# Sheet.net
KiCad netlist of a schematic drawn in Altium Designer
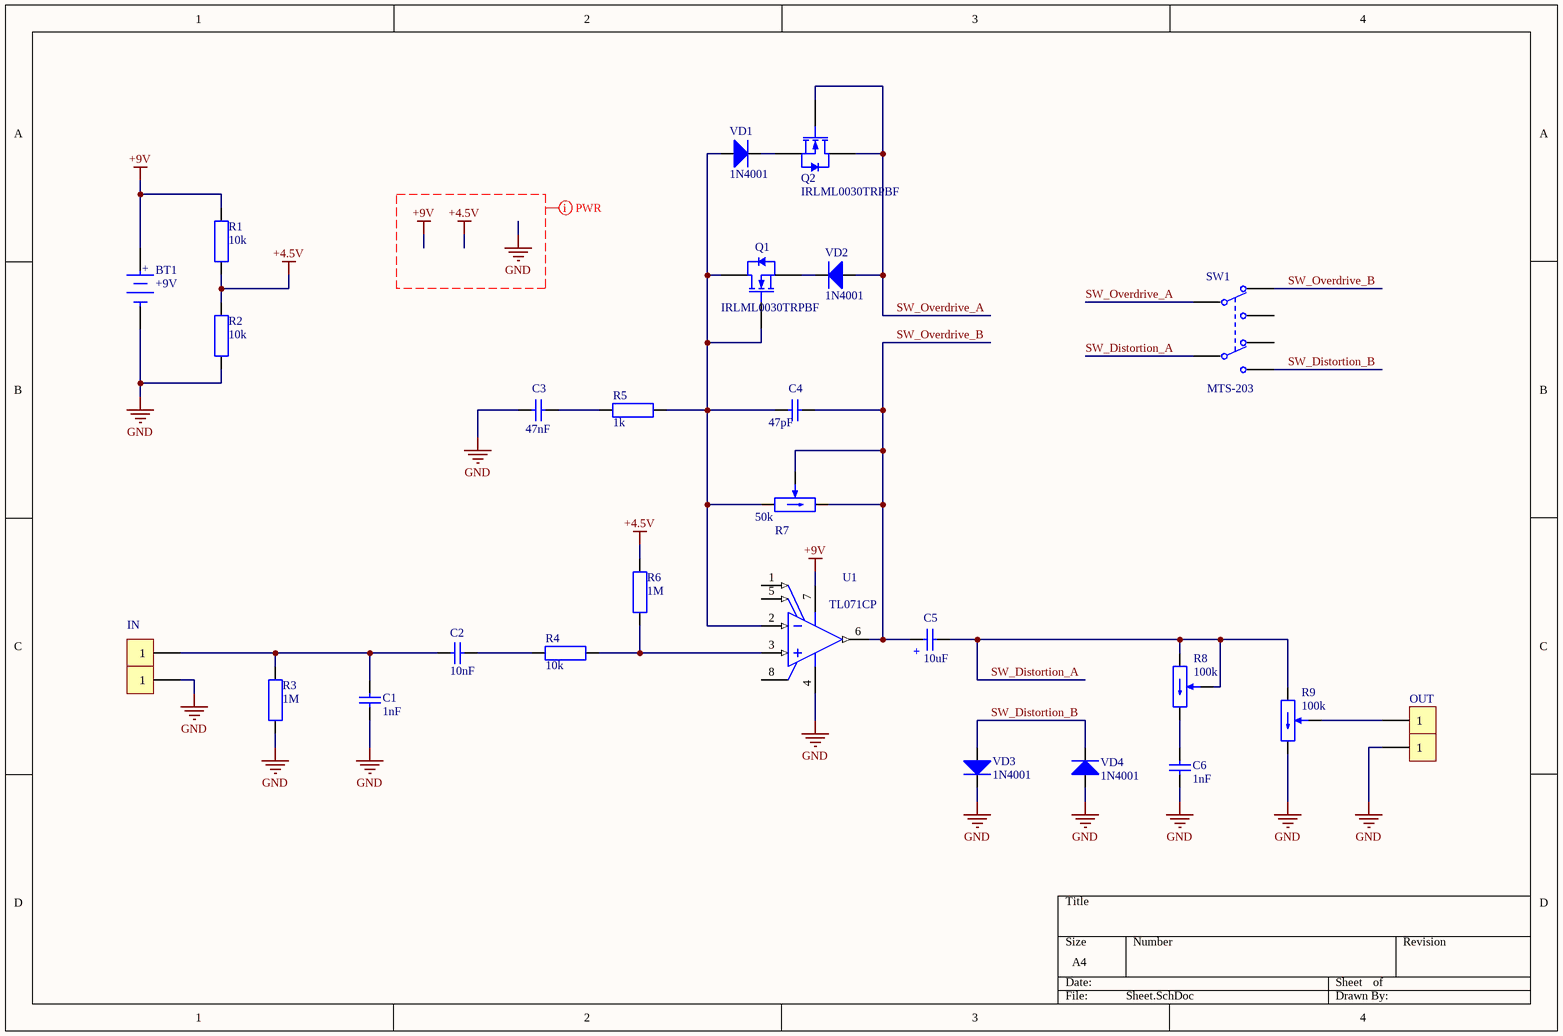
[diagram p0: Sheet.SchDoc]

(export (version "E")
  (design (tool "Eeschema 10.0.6"))
  (components
    (comp (ref "BT1")
      (value "+9V")
      (footprint "Power socket Mirrored")
      (libsource (lib "AD_lib_ISO") (part "Battery"))
    )
    (comp (ref "C1") (value "1nF") (footprint "CAP-CER-DISK") (libsource (lib "AD_lib_ISO") (part "Cap")))
    (comp (ref "C2") (value "10nF") (footprint "CAP-CER-DISK") (libsource (lib "AD_lib_ISO") (part "Cap")))
    (comp (ref "C3") (value "47nF") (footprint "CAP-CER-DISK") (libsource (lib "AD_lib_ISO") (part "Cap")))
    (comp (ref "C4") (value "47pF") (footprint "CAP-CER-DISK") (libsource (lib "AD_lib_ISO") (part "Cap")))
    (comp (ref "C5")
      (value "10uF")
      (footprint "CAP-ELEC-5x11mm")
      (libsource (lib "AD_lib_ISO") (part "Cap_Polar"))
    )
    (comp (ref "C6") (value "1nF") (footprint "CAP-CER-DISK") (libsource (lib "AD_lib_ISO") (part "Cap")))
    (comp (ref "IN+") (value "IN") (footprint "PLS-1") (libsource (lib "") (part "PLS-1_1")))
    (comp (ref "IN-") (value "PLS-1") (footprint "PLS-1") (libsource (lib "") (part "PLS-1_1")))
    (comp (ref "OUT+") (value "OUT") (footprint "PLS-1") (libsource (lib "AD_lib_ISO") (part "PLS-1")))
    (comp (ref "OUT-") (value "OUT") (footprint "PLS-1") (libsource (lib "AD_lib_ISO") (part "PLS-1")))
    (comp (ref "Q1")
      (value "IRLML0030TRPBF")
      (footprint "TO220 - HORIZONTAL")
      (fields (field (name "MANUFACTURER") "Infineon Technologies") (field (name "AUTHOR") "Tarasov Maxim"))
      (libsource (lib "AD_lib_ISO") (part "MOSFET N-CH"))
    )
    (comp (ref "Q2")
      (value "IRLML0030TRPBF")
      (footprint "TO220 - HORIZONTAL")
      (fields (field (name "MANUFACTURER") "Infineon Technologies") (field (name "AUTHOR") "Tarasov Maxim"))
      (libsource (lib "AD_lib_ISO") (part "MOSFET N-CH"))
    )
    (comp (ref "R1") (value "10k") (footprint "Res-Axis") (libsource (lib "AD_lib_ISO") (part "Res")))
    (comp (ref "R2") (value "10k") (footprint "Res-Axis") (libsource (lib "AD_lib_ISO") (part "Res")))
    (comp (ref "R3") (value "1M") (footprint "Res-Axis") (libsource (lib "AD_lib_ISO") (part "Res")))
    (comp (ref "R4") (value "10k") (footprint "Res-Axis") (libsource (lib "") (part "Res_1")))
    (comp (ref "R5") (value "1k") (footprint "Res-Axis") (libsource (lib "") (part "Res_1")))
    (comp (ref "R6") (value "1M") (footprint "Res-Axis") (libsource (lib "AD_lib_ISO") (part "Res")))
    (comp (ref "R7") (value "50k") (footprint "RES-POT-2") (libsource (lib "") (part "Res_Pot_1")))
    (comp (ref "R8") (value "100k") (footprint "RES-POT-2") (libsource (lib "AD_lib_ISO") (part "Res_Pot")))
    (comp (ref "R9") (value "100k") (footprint "RES-POT-2") (libsource (lib "AD_lib_ISO") (part "Res_Pot")))
    (comp (ref "SW1")
      (value "MTS-203")
      (footprint "MTS-203")
      (description "DPDT")
      (libsource (lib "AD_lib_ISO") (part "MTS-203"))
    )
    (comp (ref "U1")
      (value "TL071CP")
      (footprint "DIP-8")
      (fields (field (name "MANUFACTURER") "Texas Instruments"))
      (libsource (lib "AD_lib_ISO") (part "TL071CP"))
    )
    (comp (ref "VD1") (value "1N4001") (footprint "DIODE-AXIS") (libsource (lib "AD_lib_ISO") (part "Diode")))
    (comp (ref "VD2") (value "1N4001") (footprint "DIODE-AXIS") (libsource (lib "AD_lib_ISO") (part "Diode")))
    (comp (ref "VD3") (value "1N4001") (footprint "DIODE-AXIS") (libsource (lib "AD_lib_ISO") (part "Diode")))
    (comp (ref "VD4") (value "1N4001") (footprint "DIODE-AXIS") (libsource (lib "AD_lib_ISO") (part "Diode")))
  )
  (nets
    (net (code "1") (name "+4.5V") (class "Default")
      (node (ref "R1") (pin "1") (pinfunction "1_1") (pintype "passive"))
      (node (ref "R2") (pin "2") (pinfunction "2_2") (pintype "passive"))
      (node (ref "R6") (pin "2") (pinfunction "2_2") (pintype "passive"))
    )
    (net (code "2") (name "+9V") (class "Default")
      (node (ref "BT1") (pin "V") (pinfunction "A_V") (pintype "passive"))
      (node (ref "R1") (pin "2") (pinfunction "2_2") (pintype "passive"))
      (node (ref "U1") (pin "7") (pinfunction "VCC+_7") (pintype "power_in"))
    )
    (net (code "3") (name "/SW_Distortion_A") (class "Default")
      (node (ref "C5") (pin "C") (pinfunction "C_C") (pintype "passive"))
      (node (ref "R8") (pin "1") (pinfunction "CCW_1") (pintype "passive"))
      (node (ref "R8") (pin "3") (pinfunction "W_3") (pintype "passive"))
      (node (ref "R9") (pin "1") (pinfunction "CCW_1") (pintype "passive"))
      (node (ref "SW1") (pin "5") (pinfunction "5_5") (pintype "passive"))
    )
    (net (code "4") (name "/SW_Distortion_B") (class "Default")
      (node (ref "SW1") (pin "6") (pinfunction "6_6") (pintype "passive"))
      (node (ref "VD3") (pin "A") (pinfunction "A_A") (pintype "passive"))
      (node (ref "VD4") (pin "C") (pinfunction "C_C") (pintype "passive"))
    )
    (net (code "5") (name "/SW_Overdrive_A") (class "Default")
      (node (ref "Q2") (pin "1") (pinfunction "G_1") (pintype "passive"))
      (node (ref "Q2") (pin "2") (pinfunction "D_2") (pintype "passive"))
      (node (ref "SW1") (pin "2") (pinfunction "2_2") (pintype "passive"))
      (node (ref "VD2") (pin "A") (pinfunction "A_A") (pintype "passive"))
    )
    (net (code "6") (name "/SW_Overdrive_B") (class "Default")
      (node (ref "C4") (pin "2") (pinfunction "2_2") (pintype "passive"))
      (node (ref "C5") (pin "A") (pinfunction "A_A") (pintype "passive"))
      (node (ref "R7") (pin "2") (pinfunction "CW_2") (pintype "passive"))
      (node (ref "R7") (pin "3") (pinfunction "W_3") (pintype "passive"))
      (node (ref "SW1") (pin "3") (pinfunction "3_3") (pintype "passive"))
      (node (ref "U1") (pin "6") (pinfunction "OUT_6") (pintype "output"))
    )
    (net (code "7") (name "GND") (class "Default")
      (node (ref "BT1") (pin "G") (pinfunction "C_G") (pintype "passive"))
      (node (ref "C1") (pin "2") (pinfunction "2_2") (pintype "passive"))
      (node (ref "C3") (pin "1") (pinfunction "1_1") (pintype "passive"))
      (node (ref "C6") (pin "2") (pinfunction "2_2") (pintype "passive"))
      (node (ref "IN-") (pin "1") (pinfunction "1_1") (pintype "passive"))
      (node (ref "OUT-") (pin "1") (pinfunction "1_1") (pintype "passive"))
      (node (ref "R2") (pin "1") (pinfunction "1_1") (pintype "passive"))
      (node (ref "R3") (pin "1") (pinfunction "1_1") (pintype "passive"))
      (node (ref "R9") (pin "2") (pinfunction "CW_2") (pintype "passive"))
      (node (ref "U1") (pin "4") (pinfunction "VCC-_4") (pintype "power_in"))
      (node (ref "VD3") (pin "C") (pinfunction "C_C") (pintype "passive"))
      (node (ref "VD4") (pin "A") (pinfunction "A_A") (pintype "passive"))
    )
    (net (code "8") (name "Net-(C1-Pad1)") (class "Default")
      (node (ref "C1") (pin "1") (pinfunction "1_1") (pintype "passive"))
      (node (ref "C2") (pin "2") (pinfunction "2_2") (pintype "passive"))
      (node (ref "IN+") (pin "1") (pinfunction "1_1") (pintype "passive"))
      (node (ref "R3") (pin "2") (pinfunction "2_2") (pintype "passive"))
    )
    (net (code "9") (name "Net-(C2-Pad1)") (class "Default")
      (node (ref "C2") (pin "1") (pinfunction "1_1") (pintype "passive"))
      (node (ref "R4") (pin "1") (pinfunction "1_1") (pintype "passive"))
    )
    (net (code "10") (name "Net-(C3-Pad2)") (class "Default")
      (node (ref "C3") (pin "2") (pinfunction "2_2") (pintype "passive"))
      (node (ref "R5") (pin "1") (pinfunction "1_1") (pintype "passive"))
    )
    (net (code "11") (name "Net-(Q1-D)") (class "Default")
      (node (ref "C4") (pin "1") (pinfunction "1_1") (pintype "passive"))
      (node (ref "Q1") (pin "1") (pinfunction "G_1") (pintype "passive"))
      (node (ref "Q1") (pin "2") (pinfunction "D_2") (pintype "passive"))
      (node (ref "R5") (pin "2") (pinfunction "2_2") (pintype "passive"))
      (node (ref "R7") (pin "1") (pinfunction "CCW_1") (pintype "passive"))
      (node (ref "U1") (pin "2") (pinfunction "IN-_2") (pintype "input"))
      (node (ref "VD1") (pin "A") (pinfunction "A_A") (pintype "passive"))
    )
    (net (code "12") (name "Net-(Q1-S)") (class "Default")
      (node (ref "Q1") (pin "3") (pinfunction "S_3") (pintype "passive"))
      (node (ref "VD2") (pin "C") (pinfunction "C_C") (pintype "passive"))
    )
    (net (code "13") (name "Net-(Q2-S)") (class "Default")
      (node (ref "Q2") (pin "3") (pinfunction "S_3") (pintype "passive"))
      (node (ref "VD1") (pin "C") (pinfunction "C_C") (pintype "passive"))
    )
    (net (code "14") (name "Net-(R8-CW)") (class "Default")
      (node (ref "C6") (pin "1") (pinfunction "1_1") (pintype "passive"))
      (node (ref "R8") (pin "2") (pinfunction "CW_2") (pintype "passive"))
    )
    (net (code "15") (name "Net-(R9-W)") (class "Default")
      (node (ref "OUT+") (pin "1") (pinfunction "1_1") (pintype "passive"))
      (node (ref "R9") (pin "3") (pinfunction "W_3") (pintype "passive"))
    )
    (net (code "16") (name "Net-(U1-IN+)") (class "Default")
      (node (ref "R4") (pin "2") (pinfunction "2_2") (pintype "passive"))
      (node (ref "R6") (pin "1") (pinfunction "1_1") (pintype "passive"))
      (node (ref "U1") (pin "3") (pinfunction "IN+_3") (pintype "input"))
    )
    (net (code "17") (name "unconnected-(SW1-Pad1)") (class "Default")
      (node (ref "SW1") (pin "1") (pinfunction "1_1") (pintype "passive"))
    )
    (net (code "18") (name "unconnected-(SW1-Pad4)") (class "Default")
      (node (ref "SW1") (pin "4") (pinfunction "4_4") (pintype "passive"))
    )
    (net (code "19") (name "unconnected-(U1-NC-Pad8)") (class "Default")
      (node (ref "U1") (pin "8") (pinfunction "NC_8") (pintype "passive"))
    )
    (net (code "20") (name "unconnected-(U1-OFFSET_N1-Pad1)") (class "Default")
      (node (ref "U1") (pin "1") (pinfunction "OFFSET_N1_1") (pintype "input"))
    )
    (net (code "21") (name "unconnected-(U1-OFFSET_N2-Pad5)") (class "Default")
      (node (ref "U1") (pin "5") (pinfunction "OFFSET_N2_5") (pintype "input"))
    )
  )
)
